# NiMH_Battery_Charger.net
KiCad netlist of a schematic drawn in Altium Designer
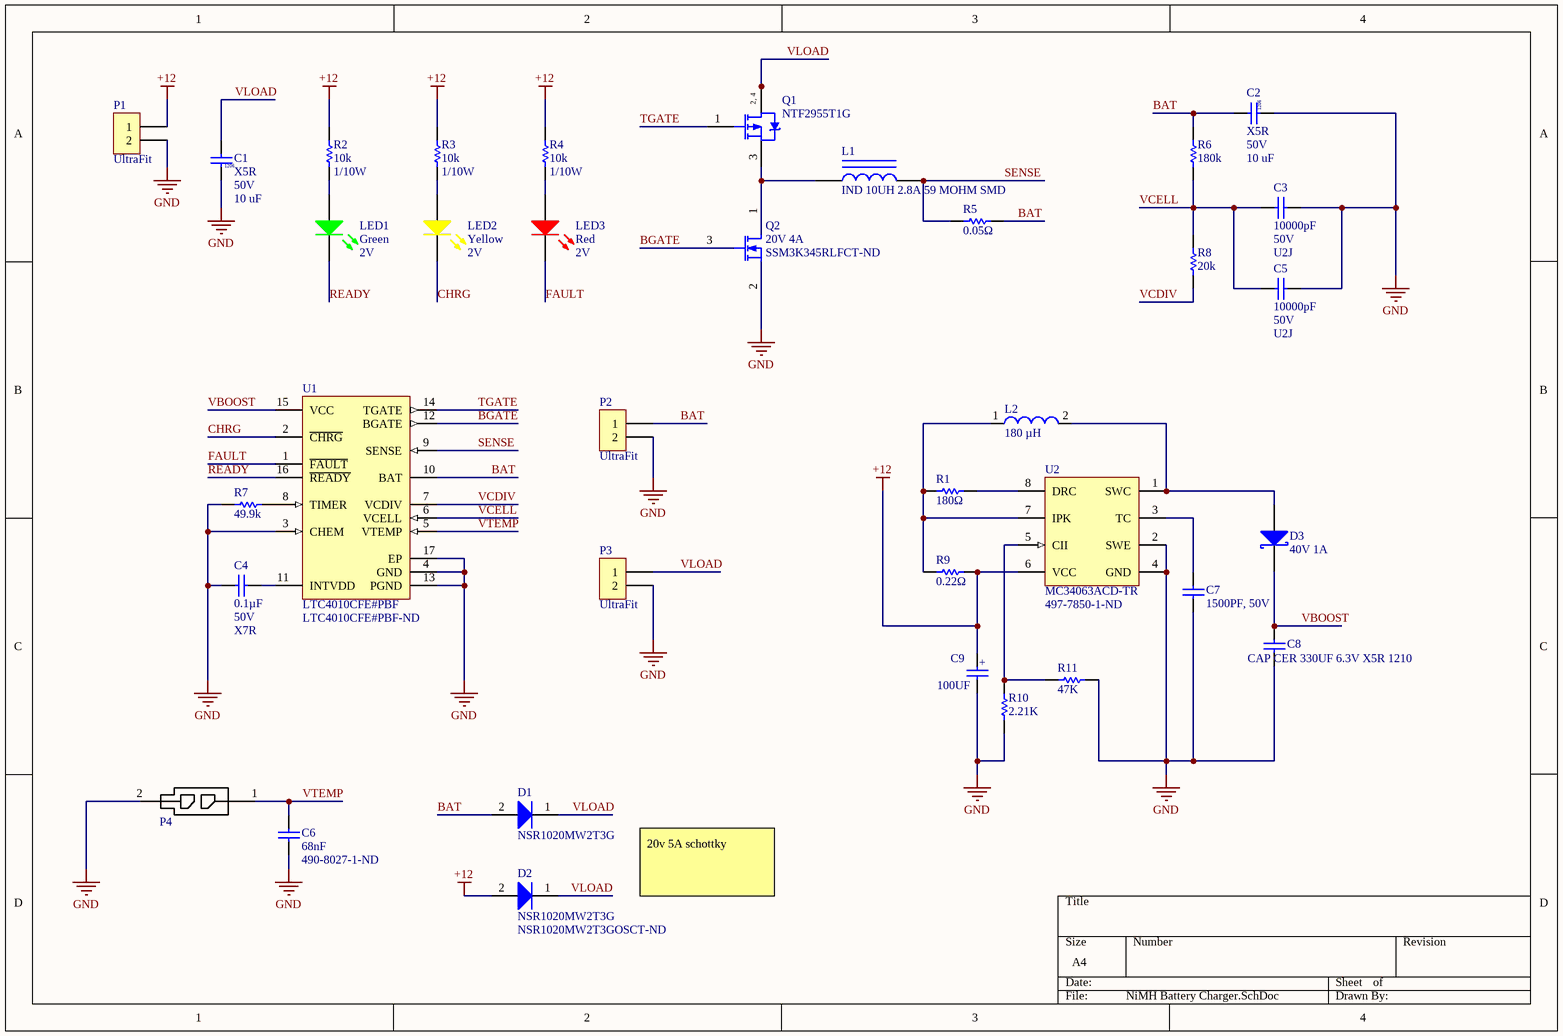
[diagram p0: NiMH Battery Charger.SchDoc]

(export (version "E")
  (design (tool "Eeschema 10.0.6"))
  (components
    (comp (ref "C1")
      (value "CAP CER 10uF 50V 20% X5R 1206")
      (footprint "CAP, 1206")
      (description "10µF ±20% 50V Ceramic Capacitor X5R 1206 (3216 Metric)")
      (fields
        (field (name "MANUFACTURER") "Murata")
        (field (name "TOLERANCE") "20%")
        (field (name "RATING") "X5R")
        (field (name "VOLTAGE RATING") "50V")
        (field (name "CAPACITANCE") "10 uF")
      )
      (libsource (lib "Schematic Diagrams") (part "CAP CER 10uF 50V 20% X5R 1206"))
    )
    (comp (ref "C2")
      (value "CAP CER 10uF 50V 20% X5R 1206")
      (footprint "CAP, 1206")
      (description "10µF ±20% 50V Ceramic Capacitor X5R 1206 (3216 Metric)")
      (fields
        (field (name "MANUFACTURER") "Murata")
        (field (name "TOLERANCE") "20%")
        (field (name "RATING") "X5R")
        (field (name "VOLTAGE RATING") "50V")
        (field (name "CAPACITANCE") "10 uF")
      )
      (libsource (lib "Schematic Diagrams") (part "CAP CER 10uF 50V 20% X5R 1206"))
    )
    (comp (ref "C3")
      (value "CAP CER 10nF 50V 5% X7R 0603")
      (footprint "CAP, 0603")
      (description "10000pF ±5% 50V Ceramic Capacitor U2J 0603 (1608 Metric)")
      (fields
        (field (name "TOLERANCE") "±5%")
        (field (name "CAPACITANCE") "10000pF")
        (field (name "VOLTAGE") "50V")
        (field (name "TEMPERATURE COEFFICIENT") "U2J")
      )
      (libsource (lib "Schematic Diagrams") (part "CAP CER 10nF 50V 5% X7R 0603"))
    )
    (comp (ref "C4")
      (value "CAP CER 0.1UF 50V 10% X7R 0603")
      (footprint "CAP, 0603")
      (description "0.10µF ±10% 50V Ceramic Capacitor X7R 0603 (1608 Metric)")
      (fields
        (field (name "TOLERANCE") "±10%")
        (field (name "CAPACITANCE") "0.1µF")
        (field (name "VOLTAGE") "50V")
        (field (name "TEMPERATURE COEFFICIENT") "X7R")
      )
      (libsource (lib "Schematic Diagrams") (part "CAP CER 0.1UF 50V 10% X7R 0603"))
    )
    (comp (ref "C5")
      (value "CAP CER 10nF 50V 5% X7R 0603")
      (footprint "CAP, 0603")
      (description "10000pF ±5% 50V Ceramic Capacitor U2J 0603 (1608 Metric)")
      (fields
        (field (name "TOLERANCE") "±5%")
        (field (name "CAPACITANCE") "10000pF")
        (field (name "VOLTAGE") "50V")
        (field (name "TEMPERATURE COEFFICIENT") "U2J")
      )
      (libsource (lib "Schematic Diagrams") (part "CAP CER 10nF 50V 5% X7R 0603"))
    )
    (comp (ref "C6")
      (value "68nF")
      (footprint "CAP, 0603")
      (description "0.068µF 50V Ceramic Capacitor X7R 0603 (1608 Metric) 0.063\" L x 0.032\" W (1.60mm x 0.80mm)")
      (fields
        (field (name "MANUFACTURER") "Murata")
        (field (name "MANUFACTURER PART NUMBER") "GCM188R71H683KA57D")
        (field (name "SUPPLIER PART NUMBER 1") "490-8027-1-ND")
      )
      (libsource (lib "Schematic Diagrams") (part "CAP CER 0.068UF 10% 50V X7R 0603"))
    )
    (comp (ref "C7")
      (value "1500PF, 50V")
      (footprint "CAP, 0603")
      (description "KEMET - C0603C152K5RACTU - CAP, 1500PF, 50V, 10%, X7R, 0603")
      (fields (field (name "TOLERANCE") "10%") (field (name "VOLTAGE") "50V"))
      (libsource (lib "Schematic Diagrams") (part "CAP, 1500PF, 50V, 10%, X7R, 0603"))
    )
    (comp (ref "C8")
      (value "CAP CER 330UF 6.3V X5R 1210")
      (footprint "CAP, 1210")
      (description "330µF ±20% 6.3V Ceramic Capacitor X5R 1210 (3225 Metric)")
      (fields
        (field (name "MANUFACTURER") "Taiyo Yuden")
        (field (name "MANUFACTURER PART NUMBER") "JMK325ABJ337MM-P")
      )
      (libsource (lib "Schematic Diagrams") (part "CAP CER 330UF 6.3V X5R 1210"))
    )
    (comp (ref "C9")
      (value "100UF")
      (footprint "CAP ALUM 6.3MM RADIAL SMD")
      (description "100µF 35V Aluminum Electrolytic Capacitors Radial, Can - SMD 2000 Hrs @ 85°C")
      (fields (field (name "TOLERANCE") "20%") (field (name "VOLTAGE") "35V"))
      (libsource (lib "Schematic Diagrams") (part "CAP ALUM 100UF 20% 35V SMD"))
    )
    (comp (ref "D1")
      (value "NSR1020MW2T3G")
      (footprint "ONSC-SOD-323-2-477-02_V")
      (description "Schottky Barrier Diode, 2-Pin SOD-323, Pb-Free, Tape and Reel")
      (fields (field (name "MANUFACTURER") "On Semiconductor"))
      (libsource (lib "Schematic Diagrams") (part "ONSC-D-K1A2-2"))
    )
    (comp (ref "D2")
      (value "NSR1020MW2T3G")
      (footprint "ONSC-SOD-323-2-477-02_V")
      (description "Schottky Barrier Diode, 2-Pin SOD-323, Pb-Free, Tape and Reel")
      (fields
        (field (name "MANUFACTURER") "On Semiconductor")
        (field (name "SUPPLIER PART NUMBER 1") "NSR1020MW2T3GOSCT-ND")
      )
      (libsource (lib "Schematic Diagrams") (part "DIODE Schottky Barrier 20V"))
    )
    (comp (ref "D3")
      (value "40V 1A")
      (footprint "MELF")
      (description "Diode Schottky 40V 1A Surface Mount MELF")
      (libsource (lib "Schematic Diagrams") (part "DIODE SCHOTTKY 40V 1A MELF"))
    )
    (comp (ref "L1")
      (value "IND 10UH 2.8A 59 MOHM SMD")
      (footprint "INDP100102X31N")
      (description "10µH Shielded Inductor 2.8A 59 mOhm Max Nonstandard")
      (fields
        (field (name "MANUFACTURER") "Sumida")
        (field (name "MANUFACTURER PART NUMBER") "CDRH103RNP-100NC-B")
      )
      (libsource (lib "Schematic Diagrams") (part "IND 10UH 2.8A 59 MOHM SMD"))
    )
    (comp (ref "L2")
      (value "180 µH")
      (footprint "WE-PD-XL")
      (description "SMD-Shielded Power Inductor WE-PD, L = 180 µH")
      (libsource (lib "Schematic Diagrams") (part "IND 180 µH Power Inductor"))
    )
    (comp (ref "LED1")
      (value "LED GREEN CLEAR 2V 0603")
      (footprint "LED_0603")
      (description "Green 572nm LED Indication - Discrete 2V 0603 (1608 Metric)")
      (fields
        (field (name "MANUFACTURER") "Wurth Electronics Inc.")
        (field (name "MANUFACTURER PART NUMBER") "150060VS75000")
        (field (name "COLOR") "Green")
        (field (name "VOLTAGE - FORWARD (VF) (TYP)") "2V")
      )
      (libsource (lib "Schematic Diagrams") (part "LED GREEN CLEAR 2V 0603"))
    )
    (comp (ref "LED2")
      (value "LED YELLOW CLEAR 2.1V 0603")
      (footprint "LED_0603")
      (description "Yellow 590nm LED Indication - Discrete 2V 0603 (1608 Metric)")
      (fields
        (field (name "MANUFACTURER") "Wurth Electronics Inc.")
        (field (name "MANUFACTURER PART NUMBER") "150060YS75000")
        (field (name "COLOR") "Yellow")
        (field (name "VOLTAGE - FORWARD (VF) (TYP)") "2V")
      )
      (libsource (lib "Schematic Diagrams") (part "LED YELLOW CLEAR 2.1V 0603"))
    )
    (comp (ref "LED3")
      (value "LED RED CLEAR 2V 0603")
      (footprint "LED_0603")
      (description "Red 631nm LED Indication - Discrete 2V 0603 (1608 Metric)")
      (fields
        (field (name "MANUFACTURER") "Wurth Electronics Inc.")
        (field (name "MANUFACTURER PART NUMBER") "150060RS75000")
        (field (name "COLOR") "Red")
        (field (name "VOLTAGE - FORWARD (VF) (TYP)") "2V")
      )
      (libsource (lib "Schematic Diagrams") (part "LED RED CLEAR 2V 0603"))
    )
    (comp (ref "P1")
      (value "CONN 2POS ULTRA-FIT 0.138\"")
      (footprint "CONN, 2POS ULTRA-FIT")
      (description "Connector Header Through Hole 2 position 0.138\" (3.50mm)")
      (fields
        (field (name "MANUFACTURER") "Molex")
        (field (name "MANUFACTURER PART NUMBER") "1722871102")
        (field (name "SERIES") "UltraFit")
      )
      (libsource (lib "Schematic Diagrams") (part "CONN 2POS ULTRA-FIT 0.138{dblquote}"))
    )
    (comp (ref "P2")
      (value "CONN 2POS ULTRA-FIT 0.138\"")
      (footprint "CONN, 2POS ULTRA-FIT")
      (description "Connector Header Through Hole 2 position 0.138\" (3.50mm)")
      (fields
        (field (name "MANUFACTURER") "Molex")
        (field (name "MANUFACTURER PART NUMBER") "1722871102")
        (field (name "SERIES") "UltraFit")
      )
      (libsource (lib "Schematic Diagrams") (part "CONN 2POS ULTRA-FIT 0.138{dblquote}"))
    )
    (comp (ref "P3")
      (value "CONN 2POS ULTRA-FIT 0.138\"")
      (footprint "CONN, 2POS ULTRA-FIT")
      (description "Connector Header Through Hole 2 position 0.138\" (3.50mm)")
      (fields
        (field (name "MANUFACTURER") "Molex")
        (field (name "MANUFACTURER PART NUMBER") "1722871102")
        (field (name "SERIES") "UltraFit")
      )
      (libsource (lib "Schematic Diagrams") (part "CONN 2POS ULTRA-FIT 0.138{dblquote}"))
    )
    (comp (ref "P4")
      (value "CONN 2POS MICRO-FIT 3mm")
      (footprint "CONN, 2POS MICRO-FIT")
      (description "Connector Header Through Hole 2 position")
      (fields (field (name "MANUFACTURER") "Molex") (field (name "MANUFACTURER PART NUMBER") "43045-0227"))
      (libsource (lib "Schematic Diagrams") (part "CONN 2POS MICRO-FIT 3mm"))
    )
    (comp (ref "Q1")
      (value "NTF2955T1G")
      (footprint "ONSC-SOT-223-4-318E-04_V")
      (description "Power MOSFET, -60 V, -2.6 A, Single P-Channel, 4-Pin SOT-223, Pb-Free, Tape and Reel")
      (fields (field (name "MANUFACTURER") "On Semiconductor"))
      (libsource (lib "Schematic Diagrams") (part "ONSC-PMOS-G1D2S3D4-4"))
    )
    (comp (ref "Q2")
      (value "20V 4A")
      (footprint "SOT23")
      (description "N-Channel 20V 4A (Ta) 1W (Ta) Surface Mount SOT-23F")
      (fields (field (name "SUPPLIER PART NUMBER 1") "SSM3K345RLFCT-ND"))
      (libsource (lib "Schematic Diagrams") (part "MOSFET N-CHANNEL 20V 4A SOT23F"))
    )
    (comp (ref "R1")
      (value "180Ω")
      (footprint "RES, 0603")
      (fields (field (name "MANUFACTURER") "Vishay Dale") (field (name "PART NUMBER") "CRCW0402180KFKED"))
      (libsource (lib "Schematic Diagrams") (part "RES 180k Ohms"))
    )
    (comp (ref "R2")
      (value "RES 10K OHM 1% 1/10W 0603")
      (footprint "RES, 0603")
      (description "RES SMD 10K OHM 1% 1/10W 0603")
      (fields
        (field (name "TOLERANCE") "±1%")
        (field (name "RESISTANCE") "10k")
        (field (name "POWER") "1/10W")
      )
      (libsource (lib "Schematic Diagrams") (part "RES 10K OHM 1% 1/10W 0603"))
    )
    (comp (ref "R3")
      (value "RES 10K OHM 1% 1/10W 0603")
      (footprint "RES, 0603")
      (description "RES SMD 10K OHM 1% 1/10W 0603")
      (fields
        (field (name "TOLERANCE") "±1%")
        (field (name "RESISTANCE") "10k")
        (field (name "POWER") "1/10W")
      )
      (libsource (lib "Schematic Diagrams") (part "RES 10K OHM 1% 1/10W 0603"))
    )
    (comp (ref "R4")
      (value "RES 10K OHM 1% 1/10W 0603")
      (footprint "RES, 0603")
      (description "RES SMD 10K OHM 1% 1/10W 0603")
      (fields
        (field (name "TOLERANCE") "±1%")
        (field (name "RESISTANCE") "10k")
        (field (name "POWER") "1/10W")
      )
      (libsource (lib "Schematic Diagrams") (part "RES 10K OHM 1% 1/10W 0603"))
    )
    (comp (ref "R5")
      (value "0.05Ω")
      (footprint "RES, 0603")
      (description "Chip Resistor, 50 mOhm, +/- 1%, 1 W, -65 to 170 degC, 2512 (6432 Metric), RoHS, Tape and Reel")
      (fields (field (name "MANUFACTURER") "Vishay"))
      (libsource (lib "Schematic Diagrams") (part "RES-2"))
    )
    (comp (ref "R6")
      (value "180k")
      (footprint "RES, 0603")
      (fields (field (name "MANUFACTURER") "Vishay Dale") (field (name "PART NUMBER") "CRCW0402180KFKED"))
      (libsource (lib "Schematic Diagrams") (part "RES"))
    )
    (comp (ref "R7")
      (value "49.9k")
      (footprint "RES, 0603")
      (fields (field (name "MANUFACTURER") "Bourns") (field (name "PART NUMBER") "CR0402-FX-4992GLF"))
      (libsource (lib "Miscellaneous Devices") (part "RES"))
    )
    (comp (ref "R8")
      (value "20k")
      (footprint "RES, 0603")
      (fields (field (name "PART NUMBER") "CRCW040220K0FKED") (field (name "MANUFACTURER") "Vishay Dale"))
      (libsource (lib "Schematic Diagrams") (part "RES"))
    )
    (comp (ref "R9")
      (value "0.22Ω")
      (footprint "RES, 0603")
      (fields (field (name "MANUFACTURER") "Vishay Dale") (field (name "PART NUMBER") "CRCW0402180KFKED"))
      (libsource (lib "Schematic Diagrams") (part "RES 180k Ohms"))
    )
    (comp (ref "R10")
      (value "2.21K")
      (footprint "RES, 0603")
      (fields
        (field (name "MANUFACTURER") "Yageo")
        (field (name "MANUFACTURER PART NUMBER") "AC0603FR-072K21L")
        (field (name "TOLERANCE") "1%")
      )
      (libsource (lib "Schematic Diagrams") (part "RES 2.21K OHM 1% 1/10W 0603"))
    )
    (comp (ref "R11")
      (value "47K")
      (footprint "RES, 0603")
      (description "RES SMD 47K OHM 1% 1/10W 0603")
      (fields (field (name "TOLERANCE") "1%"))
      (libsource (lib "Schematic Diagrams") (part "RES 47K OHM 1% 1/10W 0603"))
    )
    (comp (ref "U1")
      (value "LTC4010CFE#PBF")
      (footprint "Footprints:LT-FE-16-EPV-BC_L")
      (fields
        (field (name "MANUFACTURER") "Linear Technology")
        (field (name "SUPPLIER PART NUMBER 1") "LTC4010CFE#PBF-ND")
      )
      (libsource (lib "Schematic Diagrams") (part "IC Nickel Battery Charger"))
    )
    (comp (ref "U2")
      (value "MC34063ACD-TR")
      (footprint "SO8_N")
      (description "DC/DC converter control circuit, 8-Pin SO, Tape and Reel")
      (fields (field (name "SUPPLIER PART NUMBER 1") "497-7850-1-ND"))
      (libsource (lib "Schematic Diagrams") (part "IC Buck boost converter MC34063"))
    )
  )
  (nets
    (net (code "1") (name "+12") (class "Default")
      (node (ref "C9") (pin "1") (pinfunction "1_1") (pintype "passive"))
      (node (ref "D2") (pin "2") (pinfunction "A_2") (pintype "passive"))
      (node (ref "P1") (pin "1") (pinfunction "1_1") (pintype "passive"))
      (node (ref "R2") (pin "1") (pinfunction "1_1") (pintype "passive"))
      (node (ref "R3") (pin "1") (pinfunction "1_1") (pintype "passive"))
      (node (ref "R4") (pin "1") (pinfunction "1_1") (pintype "passive"))
      (node (ref "R9") (pin "1") (pinfunction "1_1") (pintype "passive"))
      (node (ref "U2") (pin "6") (pinfunction "VCC_6") (pintype "power_in"))
    )
    (net (code "2") (name "/BAT") (class "Default")
      (node (ref "C2") (pin "1") (pinfunction "1_1") (pintype "passive"))
      (node (ref "D1") (pin "2") (pinfunction "A_2") (pintype "passive"))
      (node (ref "P2") (pin "1") (pinfunction "1_1") (pintype "passive"))
      (node (ref "R5") (pin "2") (pinfunction "2_2") (pintype "passive"))
      (node (ref "R6") (pin "2") (pinfunction "2_2") (pintype "passive"))
      (node (ref "U1") (pin "10") (pinfunction "BAT_10") (pintype "power_in"))
    )
    (net (code "3") (name "/BGATE") (class "Default")
      (node (ref "Q2") (pin "3") (pintype "passive"))
      (node (ref "U1") (pin "12") (pinfunction "BGATE_12") (pintype "output"))
    )
    (net (code "4") (name "/CHRG") (class "Default")
      (node (ref "LED2") (pin "2") (pinfunction "K_2") (pintype "passive"))
      (node (ref "U1") (pin "2") (pinfunction "~{CHRG}_2") (pintype "open_collector"))
    )
    (net (code "5") (name "/FAULT") (class "Default")
      (node (ref "LED3") (pin "2") (pinfunction "K_2") (pintype "passive"))
      (node (ref "U1") (pin "1") (pinfunction "~{FAULT}_1") (pintype "open_collector"))
    )
    (net (code "6") (name "/READY") (class "Default")
      (node (ref "LED1") (pin "2") (pinfunction "K_2") (pintype "passive"))
      (node (ref "U1") (pin "16") (pinfunction "~{READY}_16") (pintype "open_collector"))
    )
    (net (code "7") (name "/SENSE") (class "Default")
      (node (ref "L1") (pin "2") (pinfunction "2_2") (pintype "passive"))
      (node (ref "R5") (pin "1") (pinfunction "1_1") (pintype "passive"))
      (node (ref "U1") (pin "9") (pinfunction "SENSE_9") (pintype "input"))
    )
    (net (code "8") (name "/TGATE") (class "Default")
      (node (ref "Q1") (pin "1") (pinfunction "G_1") (pintype "passive"))
      (node (ref "U1") (pin "14") (pinfunction "TGATE_14") (pintype "output"))
    )
    (net (code "9") (name "/VBOOST") (class "Default")
      (node (ref "C8") (pin "1") (pinfunction "1_1") (pintype "passive"))
      (node (ref "D3") (pin "2") (pinfunction "K_2") (pintype "passive"))
      (node (ref "U1") (pin "15") (pinfunction "VCC_15") (pintype "power_in"))
    )
    (net (code "10") (name "/VCDIV") (class "Default")
      (node (ref "R8") (pin "1") (pinfunction "1_1") (pintype "passive"))
      (node (ref "U1") (pin "7") (pinfunction "VCDIV_7") (pintype "open_collector"))
    )
    (net (code "11") (name "/VCELL") (class "Default")
      (node (ref "C3") (pin "1") (pinfunction "1_1") (pintype "passive"))
      (node (ref "C5") (pin "1") (pinfunction "1_1") (pintype "passive"))
      (node (ref "R6") (pin "1") (pinfunction "1_1") (pintype "passive"))
      (node (ref "R8") (pin "2") (pinfunction "2_2") (pintype "passive"))
      (node (ref "U1") (pin "6") (pinfunction "VCELL_6") (pintype "input"))
    )
    (net (code "12") (name "/VLOAD") (class "Default")
      (node (ref "C1") (pin "1") (pinfunction "1_1") (pintype "passive"))
      (node (ref "D1") (pin "1") (pinfunction "K_1") (pintype "passive"))
      (node (ref "D2") (pin "1") (pinfunction "K_1") (pintype "passive"))
      (node (ref "P3") (pin "1") (pinfunction "1_1") (pintype "passive"))
      (node (ref "Q1") (pin "2") (pinfunction "D_2") (pintype "passive"))
      (node (ref "Q1") (pin "4") (pinfunction "D_4") (pintype "passive"))
    )
    (net (code "13") (name "/VTEMP") (class "Default")
      (node (ref "C6") (pin "1") (pinfunction "1_1") (pintype "passive"))
      (node (ref "P4") (pin "1") (pinfunction "1_1") (pintype "passive"))
      (node (ref "U1") (pin "5") (pinfunction "VTEMP_5") (pintype "input"))
    )
    (net (code "14") (name "GND") (class "Default")
      (node (ref "C1") (pin "2") (pinfunction "2_2") (pintype "passive"))
      (node (ref "C2") (pin "2") (pinfunction "2_2") (pintype "passive"))
      (node (ref "C3") (pin "2") (pinfunction "2_2") (pintype "passive"))
      (node (ref "C4") (pin "2") (pinfunction "2_2") (pintype "passive"))
      (node (ref "C5") (pin "2") (pinfunction "2_2") (pintype "passive"))
      (node (ref "C6") (pin "2") (pinfunction "2_2") (pintype "passive"))
      (node (ref "C7") (pin "2") (pinfunction "2_2") (pintype "passive"))
      (node (ref "C8") (pin "2") (pinfunction "2_2") (pintype "passive"))
      (node (ref "C9") (pin "2") (pinfunction "2_2") (pintype "passive"))
      (node (ref "P1") (pin "2") (pinfunction "2_2") (pintype "passive"))
      (node (ref "P2") (pin "2") (pinfunction "2_2") (pintype "passive"))
      (node (ref "P3") (pin "2") (pinfunction "2_2") (pintype "passive"))
      (node (ref "P4") (pin "2") (pinfunction "2_2") (pintype "passive"))
      (node (ref "Q2") (pin "2") (pintype "passive"))
      (node (ref "R10") (pin "2") (pinfunction "2_2") (pintype "passive"))
      (node (ref "R11") (pin "2") (pinfunction "2_2") (pintype "passive"))
      (node (ref "R7") (pin "1") (pinfunction "1_1") (pintype "passive"))
      (node (ref "U1") (pin "13") (pinfunction "PGND_13") (pintype "power_in"))
      (node (ref "U1") (pin "17") (pinfunction "EP_17") (pintype "power_in"))
      (node (ref "U1") (pin "3") (pinfunction "CHEM_3") (pintype "input"))
      (node (ref "U1") (pin "4") (pinfunction "GND_4") (pintype "power_in"))
      (node (ref "U2") (pin "2") (pinfunction "SWE_2") (pintype "open_emitter"))
      (node (ref "U2") (pin "4") (pinfunction "GND_4") (pintype "power_in"))
    )
    (net (code "15") (name "Net-(D3-A)") (class "Default")
      (node (ref "D3") (pin "1") (pinfunction "A_1") (pintype "passive"))
      (node (ref "L2") (pin "2") (pinfunction "2_2") (pintype "passive"))
      (node (ref "U2") (pin "1") (pinfunction "SWC_1") (pintype "open_collector"))
    )
    (net (code "16") (name "Net-(LED1-A)") (class "Default")
      (node (ref "LED1") (pin "1") (pinfunction "A_1") (pintype "passive"))
      (node (ref "R2") (pin "2") (pinfunction "2_2") (pintype "passive"))
    )
    (net (code "17") (name "Net-(LED2-A)") (class "Default")
      (node (ref "LED2") (pin "1") (pinfunction "A_1") (pintype "passive"))
      (node (ref "R3") (pin "2") (pinfunction "2_2") (pintype "passive"))
    )
    (net (code "18") (name "Net-(LED3-A)") (class "Default")
      (node (ref "LED3") (pin "1") (pinfunction "A_1") (pintype "passive"))
      (node (ref "R4") (pin "2") (pinfunction "2_2") (pintype "passive"))
    )
    (net (code "19") (name "Net-(Q1-S)") (class "Default")
      (node (ref "L1") (pin "1") (pinfunction "1_1") (pintype "passive"))
      (node (ref "Q1") (pin "3") (pinfunction "S_3") (pintype "passive"))
      (node (ref "Q2") (pin "1") (pintype "passive"))
    )
    (net (code "20") (name "Net-(U1-INTVDD)") (class "Default")
      (node (ref "C4") (pin "1") (pinfunction "1_1") (pintype "passive"))
      (node (ref "U1") (pin "11") (pinfunction "INTVDD_11") (pintype "power_in"))
    )
    (net (code "21") (name "Net-(U1-TIMER)") (class "Default")
      (node (ref "R7") (pin "2") (pinfunction "2_2") (pintype "passive"))
      (node (ref "U1") (pin "8") (pinfunction "TIMER_8") (pintype "input"))
    )
    (net (code "22") (name "Net-(U2-CII)") (class "Default")
      (node (ref "R10") (pin "1") (pinfunction "1_1") (pintype "passive"))
      (node (ref "R11") (pin "1") (pinfunction "1_1") (pintype "passive"))
      (node (ref "U2") (pin "5") (pinfunction "CII_5") (pintype "input"))
    )
    (net (code "23") (name "Net-(U2-DRC)") (class "Default")
      (node (ref "R1") (pin "1") (pinfunction "1_1") (pintype "passive"))
      (node (ref "U2") (pin "8") (pinfunction "DRC_8") (pintype "open_collector"))
    )
    (net (code "24") (name "Net-(U2-IPK)") (class "Default")
      (node (ref "L2") (pin "1") (pinfunction "1_1") (pintype "passive"))
      (node (ref "R1") (pin "2") (pinfunction "2_2") (pintype "passive"))
      (node (ref "R9") (pin "2") (pinfunction "2_2") (pintype "passive"))
      (node (ref "U2") (pin "7") (pinfunction "IPK_7") (pintype "passive"))
    )
    (net (code "25") (name "Net-(U2-TC)") (class "Default")
      (node (ref "C7") (pin "1") (pinfunction "1_1") (pintype "passive"))
      (node (ref "U2") (pin "3") (pinfunction "TC_3") (pintype "passive"))
    )
  )
)
